# control_board.net
KiCad netlist of a schematic drawn in EAGLE
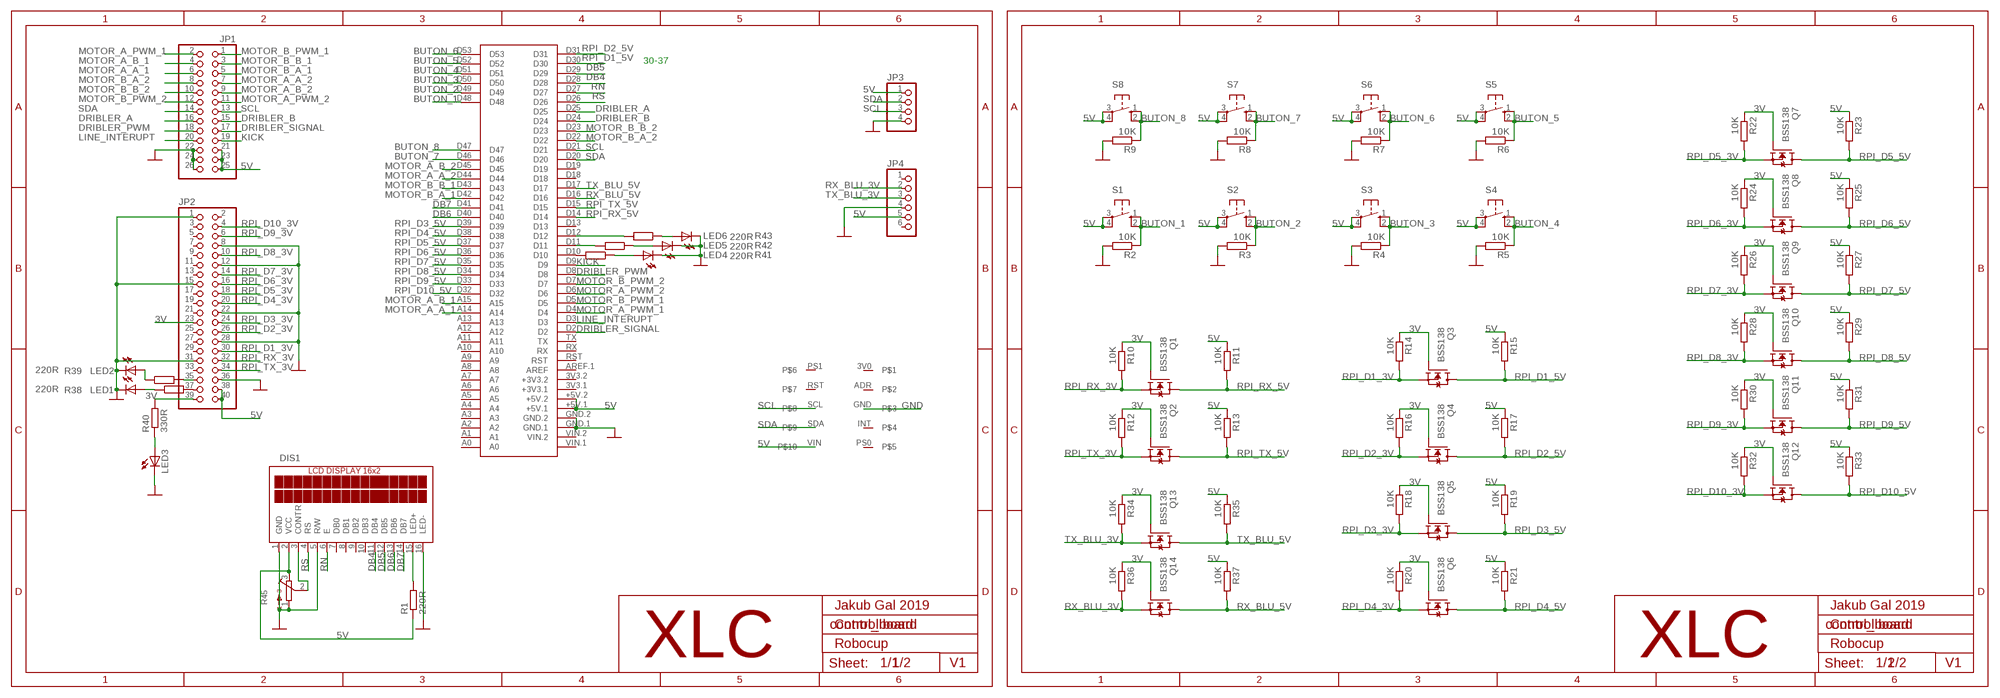
[diagram p0: schematic, sheet 1]

(export (version "E")
  (design (tool "Eeschema 10.0.6"))
  (components
    (comp (ref "DIS1")
      (value "LCD_DISPLEJ_16X2Z")
      (footprint "eagle-import:LCD_DISPLEJ_16X2")
      (libsource (lib "eagle-import") (part "LCD_DISPLEJ_16X2Z"))
    )
    (comp (ref "JP1")
      (value "PINHD-2X13_2.54")
      (footprint "eagle-import:2X13")
      (libsource (lib "eagle-import") (part "PINHD-2X13_2.54"))
    )
    (comp (ref "JP2")
      (value "PINHD-2X20_2.54")
      (footprint "eagle-import:2X20")
      (libsource (lib "eagle-import") (part "PINHD-2X20_2.54"))
    )
    (comp (ref "JP3")
      (value "PINHD-1X4_2.54")
      (footprint "eagle-import:1X04")
      (libsource (lib "eagle-import") (part "PINHD-1X4_2.54"))
    )
    (comp (ref "JP4")
      (value "PINHD-1X6_2.54")
      (footprint "eagle-import:1X06")
      (libsource (lib "eagle-import") (part "PINHD-1X6_2.54"))
    )
    (comp (ref "LED1")
      (value "LEDCHIPLED_0603")
      (footprint "eagle-import:CHIPLED_0603")
      (libsource (lib "eagle-import") (part "LEDCHIPLED_0603"))
    )
    (comp (ref "LED2")
      (value "LEDCHIPLED_0603")
      (footprint "eagle-import:CHIPLED_0603")
      (libsource (lib "eagle-import") (part "LEDCHIPLED_0603"))
    )
    (comp (ref "LED3")
      (value "LEDCHIPLED_0603")
      (footprint "eagle-import:CHIPLED_0603")
      (libsource (lib "eagle-import") (part "LEDCHIPLED_0603"))
    )
    (comp (ref "LED4")
      (value "LEDCHIPLED_0603")
      (footprint "eagle-import:CHIPLED_0603")
      (libsource (lib "eagle-import") (part "LEDCHIPLED_0603"))
    )
    (comp (ref "LED5")
      (value "LEDCHIPLED_0603")
      (footprint "eagle-import:CHIPLED_0603")
      (libsource (lib "eagle-import") (part "LEDCHIPLED_0603"))
    )
    (comp (ref "LED6")
      (value "LEDCHIPLED_0603")
      (footprint "eagle-import:CHIPLED_0603")
      (libsource (lib "eagle-import") (part "LEDCHIPLED_0603"))
    )
    (comp (ref "Q1")
      (value "BSS138")
      (footprint "eagle-import:SOT23")
      (fields (field (name "MF") "Fairchild"))
      (libsource (lib "eagle-import") (part "BSS138"))
    )
    (comp (ref "Q2")
      (value "BSS138")
      (footprint "eagle-import:SOT23")
      (fields (field (name "MF") "Fairchild"))
      (libsource (lib "eagle-import") (part "BSS138"))
    )
    (comp (ref "Q3")
      (value "BSS138")
      (footprint "eagle-import:SOT23")
      (fields (field (name "MF") "Fairchild"))
      (libsource (lib "eagle-import") (part "BSS138"))
    )
    (comp (ref "Q4")
      (value "BSS138")
      (footprint "eagle-import:SOT23")
      (fields (field (name "MF") "Fairchild"))
      (libsource (lib "eagle-import") (part "BSS138"))
    )
    (comp (ref "Q5")
      (value "BSS138")
      (footprint "eagle-import:SOT23")
      (fields (field (name "MF") "Fairchild"))
      (libsource (lib "eagle-import") (part "BSS138"))
    )
    (comp (ref "Q6")
      (value "BSS138")
      (footprint "eagle-import:SOT23")
      (fields (field (name "MF") "Fairchild"))
      (libsource (lib "eagle-import") (part "BSS138"))
    )
    (comp (ref "Q7")
      (value "BSS138")
      (footprint "eagle-import:SOT23")
      (fields (field (name "MF") "Fairchild"))
      (libsource (lib "eagle-import") (part "BSS138"))
    )
    (comp (ref "Q8")
      (value "BSS138")
      (footprint "eagle-import:SOT23")
      (fields (field (name "MF") "Fairchild"))
      (libsource (lib "eagle-import") (part "BSS138"))
    )
    (comp (ref "Q9")
      (value "BSS138")
      (footprint "eagle-import:SOT23")
      (fields (field (name "MF") "Fairchild"))
      (libsource (lib "eagle-import") (part "BSS138"))
    )
    (comp (ref "Q10")
      (value "BSS138")
      (footprint "eagle-import:SOT23")
      (fields (field (name "MF") "Fairchild"))
      (libsource (lib "eagle-import") (part "BSS138"))
    )
    (comp (ref "Q11")
      (value "BSS138")
      (footprint "eagle-import:SOT23")
      (fields (field (name "MF") "Fairchild"))
      (libsource (lib "eagle-import") (part "BSS138"))
    )
    (comp (ref "Q12")
      (value "BSS138")
      (footprint "eagle-import:SOT23")
      (fields (field (name "MF") "Fairchild"))
      (libsource (lib "eagle-import") (part "BSS138"))
    )
    (comp (ref "Q13")
      (value "BSS138")
      (footprint "eagle-import:SOT23")
      (fields (field (name "MF") "Fairchild"))
      (libsource (lib "eagle-import") (part "BSS138"))
    )
    (comp (ref "Q14")
      (value "BSS138")
      (footprint "eagle-import:SOT23")
      (fields (field (name "MF") "Fairchild"))
      (libsource (lib "eagle-import") (part "BSS138"))
    )
    (comp (ref "R1")
      (value "220R")
      (footprint "eagle-import:R0603")
      (libsource (lib "eagle-import") (part "R-EU_R0603"))
    )
    (comp (ref "R2")
      (value "10K")
      (footprint "eagle-import:R0603")
      (libsource (lib "eagle-import") (part "R-EU_R0603"))
    )
    (comp (ref "R3")
      (value "10K")
      (footprint "eagle-import:R0603")
      (libsource (lib "eagle-import") (part "R-EU_R0603"))
    )
    (comp (ref "R4")
      (value "10K")
      (footprint "eagle-import:R0603")
      (libsource (lib "eagle-import") (part "R-EU_R0603"))
    )
    (comp (ref "R5")
      (value "10K")
      (footprint "eagle-import:R0603")
      (libsource (lib "eagle-import") (part "R-EU_R0603"))
    )
    (comp (ref "R6")
      (value "10K")
      (footprint "eagle-import:R0603")
      (libsource (lib "eagle-import") (part "R-EU_R0603"))
    )
    (comp (ref "R7")
      (value "10K")
      (footprint "eagle-import:R0603")
      (libsource (lib "eagle-import") (part "R-EU_R0603"))
    )
    (comp (ref "R8")
      (value "10K")
      (footprint "eagle-import:R0603")
      (libsource (lib "eagle-import") (part "R-EU_R0603"))
    )
    (comp (ref "R9")
      (value "10K")
      (footprint "eagle-import:R0603")
      (libsource (lib "eagle-import") (part "R-EU_R0603"))
    )
    (comp (ref "R10")
      (value "10K")
      (footprint "eagle-import:R0603")
      (libsource (lib "eagle-import") (part "R-EU_R0603"))
    )
    (comp (ref "R11")
      (value "10K")
      (footprint "eagle-import:R0603")
      (libsource (lib "eagle-import") (part "R-EU_R0603"))
    )
    (comp (ref "R12")
      (value "10K")
      (footprint "eagle-import:R0603")
      (libsource (lib "eagle-import") (part "R-EU_R0603"))
    )
    (comp (ref "R13")
      (value "10K")
      (footprint "eagle-import:R0603")
      (libsource (lib "eagle-import") (part "R-EU_R0603"))
    )
    (comp (ref "R14")
      (value "10K")
      (footprint "eagle-import:R0603")
      (libsource (lib "eagle-import") (part "R-EU_R0603"))
    )
    (comp (ref "R15")
      (value "10K")
      (footprint "eagle-import:R0603")
      (libsource (lib "eagle-import") (part "R-EU_R0603"))
    )
    (comp (ref "R16")
      (value "10K")
      (footprint "eagle-import:R0603")
      (libsource (lib "eagle-import") (part "R-EU_R0603"))
    )
    (comp (ref "R17")
      (value "10K")
      (footprint "eagle-import:R0603")
      (libsource (lib "eagle-import") (part "R-EU_R0603"))
    )
    (comp (ref "R18")
      (value "10K")
      (footprint "eagle-import:R0603")
      (libsource (lib "eagle-import") (part "R-EU_R0603"))
    )
    (comp (ref "R19")
      (value "10K")
      (footprint "eagle-import:R0603")
      (libsource (lib "eagle-import") (part "R-EU_R0603"))
    )
    (comp (ref "R20")
      (value "10K")
      (footprint "eagle-import:R0603")
      (libsource (lib "eagle-import") (part "R-EU_R0603"))
    )
    (comp (ref "R21")
      (value "10K")
      (footprint "eagle-import:R0603")
      (libsource (lib "eagle-import") (part "R-EU_R0603"))
    )
    (comp (ref "R22")
      (value "10K")
      (footprint "eagle-import:R0603")
      (libsource (lib "eagle-import") (part "R-EU_R0603"))
    )
    (comp (ref "R23")
      (value "10K")
      (footprint "eagle-import:R0603")
      (libsource (lib "eagle-import") (part "R-EU_R0603"))
    )
    (comp (ref "R24")
      (value "10K")
      (footprint "eagle-import:R0603")
      (libsource (lib "eagle-import") (part "R-EU_R0603"))
    )
    (comp (ref "R25")
      (value "10K")
      (footprint "eagle-import:R0603")
      (libsource (lib "eagle-import") (part "R-EU_R0603"))
    )
    (comp (ref "R26")
      (value "10K")
      (footprint "eagle-import:R0603")
      (libsource (lib "eagle-import") (part "R-EU_R0603"))
    )
    (comp (ref "R27")
      (value "10K")
      (footprint "eagle-import:R0603")
      (libsource (lib "eagle-import") (part "R-EU_R0603"))
    )
    (comp (ref "R28")
      (value "10K")
      (footprint "eagle-import:R0603")
      (libsource (lib "eagle-import") (part "R-EU_R0603"))
    )
    (comp (ref "R29")
      (value "10K")
      (footprint "eagle-import:R0603")
      (libsource (lib "eagle-import") (part "R-EU_R0603"))
    )
    (comp (ref "R30")
      (value "10K")
      (footprint "eagle-import:R0603")
      (libsource (lib "eagle-import") (part "R-EU_R0603"))
    )
    (comp (ref "R31")
      (value "10K")
      (footprint "eagle-import:R0603")
      (libsource (lib "eagle-import") (part "R-EU_R0603"))
    )
    (comp (ref "R32")
      (value "10K")
      (footprint "eagle-import:R0603")
      (libsource (lib "eagle-import") (part "R-EU_R0603"))
    )
    (comp (ref "R33")
      (value "10K")
      (footprint "eagle-import:R0603")
      (libsource (lib "eagle-import") (part "R-EU_R0603"))
    )
    (comp (ref "R34")
      (value "10K")
      (footprint "eagle-import:R0603")
      (libsource (lib "eagle-import") (part "R-EU_R0603"))
    )
    (comp (ref "R35")
      (value "10K")
      (footprint "eagle-import:R0603")
      (libsource (lib "eagle-import") (part "R-EU_R0603"))
    )
    (comp (ref "R36")
      (value "10K")
      (footprint "eagle-import:R0603")
      (libsource (lib "eagle-import") (part "R-EU_R0603"))
    )
    (comp (ref "R37")
      (value "10K")
      (footprint "eagle-import:R0603")
      (libsource (lib "eagle-import") (part "R-EU_R0603"))
    )
    (comp (ref "R38")
      (value "220R")
      (footprint "eagle-import:R0603")
      (libsource (lib "eagle-import") (part "R-EU_R0603"))
    )
    (comp (ref "R39")
      (value "220R")
      (footprint "eagle-import:R0603")
      (libsource (lib "eagle-import") (part "R-EU_R0603"))
    )
    (comp (ref "R40")
      (value "330R")
      (footprint "eagle-import:R0603")
      (libsource (lib "eagle-import") (part "R-EU_R0603"))
    )
    (comp (ref "R41")
      (value "220R")
      (footprint "eagle-import:R0603")
      (libsource (lib "eagle-import") (part "R-EU_R0603"))
    )
    (comp (ref "R42")
      (value "220R")
      (footprint "eagle-import:R0603")
      (libsource (lib "eagle-import") (part "R-EU_R0603"))
    )
    (comp (ref "R43")
      (value "220R")
      (footprint "eagle-import:R0603")
      (libsource (lib "eagle-import") (part "R-EU_R0603"))
    )
    (comp (ref "R45")
      (value "3362P")
      (footprint "eagle-import:3362P")
      (libsource (lib "eagle-import") (part "3362P"))
    )
    (comp (ref "S1")
      (value "10-XX")
      (footprint "eagle-import:B3F-10XX")
      (fields (field (name "MPN") "B3F-1000"))
      (libsource (lib "eagle-import") (part "10-XX"))
    )
    (comp (ref "S2")
      (value "10-XX")
      (footprint "eagle-import:B3F-10XX")
      (fields (field (name "MPN") "B3F-1000"))
      (libsource (lib "eagle-import") (part "10-XX"))
    )
    (comp (ref "S3")
      (value "10-XX")
      (footprint "eagle-import:B3F-10XX")
      (fields (field (name "MPN") "B3F-1000"))
      (libsource (lib "eagle-import") (part "10-XX"))
    )
    (comp (ref "S4")
      (value "10-XX")
      (footprint "eagle-import:B3F-10XX")
      (fields (field (name "MPN") "B3F-1000"))
      (libsource (lib "eagle-import") (part "10-XX"))
    )
    (comp (ref "S5")
      (value "10-XX")
      (footprint "eagle-import:B3F-10XX")
      (fields (field (name "MPN") "B3F-1000"))
      (libsource (lib "eagle-import") (part "10-XX"))
    )
    (comp (ref "S6")
      (value "10-XX")
      (footprint "eagle-import:B3F-10XX")
      (fields (field (name "MPN") "B3F-1000"))
      (libsource (lib "eagle-import") (part "10-XX"))
    )
    (comp (ref "S7")
      (value "10-XX")
      (footprint "eagle-import:B3F-10XX")
      (fields (field (name "MPN") "B3F-1000"))
      (libsource (lib "eagle-import") (part "10-XX"))
    )
    (comp (ref "S8")
      (value "10-XX")
      (footprint "eagle-import:B3F-10XX")
      (fields (field (name "MPN") "B3F-1000"))
      (libsource (lib "eagle-import") (part "10-XX"))
    )
    (comp (ref "U$1")
      (value "MEGA2560_MIKRO")
      (footprint "eagle-import:MEGA2560_MIKRO")
      (libsource (lib "eagle-import") (part "MEGA2560_MIKRO"))
    )
    (comp (ref "U$2")
      (value "BNO055")
      (footprint "eagle-import:BNO005")
      (libsource (lib "eagle-import") (part "BNO055"))
    )
  )
  (nets
    (net (code "1") (name "/3V") (class "Default")
      (node (ref "JP2") (pin "23") (pinfunction "23_23") (pintype "passive"))
      (node (ref "JP2") (pin "39") (pinfunction "39_39") (pintype "passive"))
      (node (ref "Q1") (pin "1") (pinfunction "G_1") (pintype "passive"))
      (node (ref "Q10") (pin "1") (pinfunction "G_1") (pintype "passive"))
      (node (ref "Q11") (pin "1") (pinfunction "G_1") (pintype "passive"))
      (node (ref "Q12") (pin "1") (pinfunction "G_1") (pintype "passive"))
      (node (ref "Q13") (pin "1") (pinfunction "G_1") (pintype "passive"))
      (node (ref "Q14") (pin "1") (pinfunction "G_1") (pintype "passive"))
      (node (ref "Q2") (pin "1") (pinfunction "G_1") (pintype "passive"))
      (node (ref "Q3") (pin "1") (pinfunction "G_1") (pintype "passive"))
      (node (ref "Q4") (pin "1") (pinfunction "G_1") (pintype "passive"))
      (node (ref "Q5") (pin "1") (pinfunction "G_1") (pintype "passive"))
      (node (ref "Q6") (pin "1") (pinfunction "G_1") (pintype "passive"))
      (node (ref "Q7") (pin "1") (pinfunction "G_1") (pintype "passive"))
      (node (ref "Q8") (pin "1") (pinfunction "G_1") (pintype "passive"))
      (node (ref "Q9") (pin "1") (pinfunction "G_1") (pintype "passive"))
      (node (ref "R10") (pin "1") (pinfunction "1_1") (pintype "passive"))
      (node (ref "R12") (pin "1") (pinfunction "1_1") (pintype "passive"))
      (node (ref "R14") (pin "1") (pinfunction "1_1") (pintype "passive"))
      (node (ref "R16") (pin "1") (pinfunction "1_1") (pintype "passive"))
      (node (ref "R18") (pin "1") (pinfunction "1_1") (pintype "passive"))
      (node (ref "R20") (pin "1") (pinfunction "1_1") (pintype "passive"))
      (node (ref "R22") (pin "1") (pinfunction "1_1") (pintype "passive"))
      (node (ref "R24") (pin "1") (pinfunction "1_1") (pintype "passive"))
      (node (ref "R26") (pin "1") (pinfunction "1_1") (pintype "passive"))
      (node (ref "R28") (pin "1") (pinfunction "1_1") (pintype "passive"))
      (node (ref "R30") (pin "1") (pinfunction "1_1") (pintype "passive"))
      (node (ref "R32") (pin "1") (pinfunction "1_1") (pintype "passive"))
      (node (ref "R34") (pin "1") (pinfunction "1_1") (pintype "passive"))
      (node (ref "R36") (pin "1") (pinfunction "1_1") (pintype "passive"))
      (node (ref "R40") (pin "2") (pinfunction "2_2") (pintype "passive"))
    )
    (net (code "2") (name "/5V") (class "Default")
      (node (ref "DIS1") (pin "2") (pinfunction "VCC_2") (pintype "power_in"))
      (node (ref "JP1") (pin "21") (pinfunction "21_21") (pintype "passive"))
      (node (ref "JP1") (pin "23") (pinfunction "23_23") (pintype "passive"))
      (node (ref "JP1") (pin "25") (pinfunction "25_25") (pintype "passive"))
      (node (ref "JP2") (pin "38") (pinfunction "38_38") (pintype "passive"))
      (node (ref "JP2") (pin "40") (pinfunction "40_40") (pintype "passive"))
      (node (ref "JP3") (pin "1") (pinfunction "1_1") (pintype "passive"))
      (node (ref "JP4") (pin "5") (pinfunction "5_5") (pintype "passive"))
      (node (ref "R1") (pin "1") (pinfunction "1_1") (pintype "passive"))
      (node (ref "R11") (pin "1") (pinfunction "1_1") (pintype "passive"))
      (node (ref "R13") (pin "1") (pinfunction "1_1") (pintype "passive"))
      (node (ref "R15") (pin "1") (pinfunction "1_1") (pintype "passive"))
      (node (ref "R17") (pin "1") (pinfunction "1_1") (pintype "passive"))
      (node (ref "R19") (pin "1") (pinfunction "1_1") (pintype "passive"))
      (node (ref "R21") (pin "1") (pinfunction "1_1") (pintype "passive"))
      (node (ref "R23") (pin "1") (pinfunction "1_1") (pintype "passive"))
      (node (ref "R25") (pin "1") (pinfunction "1_1") (pintype "passive"))
      (node (ref "R27") (pin "1") (pinfunction "1_1") (pintype "passive"))
      (node (ref "R29") (pin "1") (pinfunction "1_1") (pintype "passive"))
      (node (ref "R31") (pin "1") (pinfunction "1_1") (pintype "passive"))
      (node (ref "R33") (pin "1") (pinfunction "1_1") (pintype "passive"))
      (node (ref "R35") (pin "1") (pinfunction "1_1") (pintype "passive"))
      (node (ref "R37") (pin "1") (pinfunction "1_1") (pintype "passive"))
      (node (ref "R45") (pin "3") (pinfunction "3_3") (pintype "passive"))
      (node (ref "S1") (pin "3") (pinfunction "P_3") (pintype "passive"))
      (node (ref "S1") (pin "4") (pinfunction "P1_4") (pintype "passive"))
      (node (ref "S2") (pin "3") (pinfunction "P_3") (pintype "passive"))
      (node (ref "S2") (pin "4") (pinfunction "P1_4") (pintype "passive"))
      (node (ref "S3") (pin "3") (pinfunction "P_3") (pintype "passive"))
      (node (ref "S3") (pin "4") (pinfunction "P1_4") (pintype "passive"))
      (node (ref "S4") (pin "3") (pinfunction "P_3") (pintype "passive"))
      (node (ref "S4") (pin "4") (pinfunction "P1_4") (pintype "passive"))
      (node (ref "S5") (pin "3") (pinfunction "P_3") (pintype "passive"))
      (node (ref "S5") (pin "4") (pinfunction "P1_4") (pintype "passive"))
      (node (ref "S6") (pin "3") (pinfunction "P_3") (pintype "passive"))
      (node (ref "S6") (pin "4") (pinfunction "P1_4") (pintype "passive"))
      (node (ref "S7") (pin "3") (pinfunction "P_3") (pintype "passive"))
      (node (ref "S7") (pin "4") (pinfunction "P1_4") (pintype "passive"))
      (node (ref "S8") (pin "3") (pinfunction "P_3") (pintype "passive"))
      (node (ref "S8") (pin "4") (pinfunction "P1_4") (pintype "passive"))
      (node (ref "U$1") (pin "+5V.1") (pinfunction "+5V.1_+5V.1") (pintype "bidirectional"))
      (node (ref "U$1") (pin "+5V.2") (pinfunction "+5V.2_+5V.2") (pintype "bidirectional"))
      (node (ref "U$2") (pin "VIN") (pinfunction "P$10_VIN") (pintype "bidirectional"))
    )
    (net (code "3") (name "/BUTON_1") (class "Default")
      (node (ref "R2") (pin "1") (pinfunction "1_1") (pintype "passive"))
      (node (ref "S1") (pin "1") (pinfunction "S_1") (pintype "passive"))
      (node (ref "S1") (pin "2") (pinfunction "S1_2") (pintype "passive"))
      (node (ref "U$1") (pin "D48") (pinfunction "D48_D48") (pintype "bidirectional"))
    )
    (net (code "4") (name "/BUTON_2") (class "Default")
      (node (ref "R3") (pin "1") (pinfunction "1_1") (pintype "passive"))
      (node (ref "S2") (pin "1") (pinfunction "S_1") (pintype "passive"))
      (node (ref "S2") (pin "2") (pinfunction "S1_2") (pintype "passive"))
      (node (ref "U$1") (pin "D49") (pinfunction "D49_D49") (pintype "bidirectional"))
    )
    (net (code "5") (name "/BUTON_3") (class "Default")
      (node (ref "R4") (pin "1") (pinfunction "1_1") (pintype "passive"))
      (node (ref "S3") (pin "1") (pinfunction "S_1") (pintype "passive"))
      (node (ref "S3") (pin "2") (pinfunction "S1_2") (pintype "passive"))
      (node (ref "U$1") (pin "D50") (pinfunction "D50_D50") (pintype "bidirectional"))
    )
    (net (code "6") (name "/BUTON_4") (class "Default")
      (node (ref "R5") (pin "1") (pinfunction "1_1") (pintype "passive"))
      (node (ref "S4") (pin "1") (pinfunction "S_1") (pintype "passive"))
      (node (ref "S4") (pin "2") (pinfunction "S1_2") (pintype "passive"))
      (node (ref "U$1") (pin "D51") (pinfunction "D51_D51") (pintype "bidirectional"))
    )
    (net (code "7") (name "/BUTON_5") (class "Default")
      (node (ref "R6") (pin "1") (pinfunction "1_1") (pintype "passive"))
      (node (ref "S5") (pin "1") (pinfunction "S_1") (pintype "passive"))
      (node (ref "S5") (pin "2") (pinfunction "S1_2") (pintype "passive"))
      (node (ref "U$1") (pin "D52") (pinfunction "D52_D52") (pintype "bidirectional"))
    )
    (net (code "8") (name "/BUTON_6") (class "Default")
      (node (ref "R7") (pin "1") (pinfunction "1_1") (pintype "passive"))
      (node (ref "S6") (pin "1") (pinfunction "S_1") (pintype "passive"))
      (node (ref "S6") (pin "2") (pinfunction "S1_2") (pintype "passive"))
      (node (ref "U$1") (pin "D53") (pinfunction "D53_D53") (pintype "bidirectional"))
    )
    (net (code "9") (name "/BUTON_7") (class "Default")
      (node (ref "R8") (pin "1") (pinfunction "1_1") (pintype "passive"))
      (node (ref "S7") (pin "1") (pinfunction "S_1") (pintype "passive"))
      (node (ref "S7") (pin "2") (pinfunction "S1_2") (pintype "passive"))
      (node (ref "U$1") (pin "D46") (pinfunction "D46_D46") (pintype "bidirectional"))
    )
    (net (code "10") (name "/BUTON_8") (class "Default")
      (node (ref "R9") (pin "1") (pinfunction "1_1") (pintype "passive"))
      (node (ref "S8") (pin "1") (pinfunction "S_1") (pintype "passive"))
      (node (ref "S8") (pin "2") (pinfunction "S1_2") (pintype "passive"))
      (node (ref "U$1") (pin "D47") (pinfunction "D47_D47") (pintype "bidirectional"))
    )
    (net (code "11") (name "/DB4") (class "Default")
      (node (ref "DIS1") (pin "11") (pinfunction "DB4_11") (pintype "bidirectional"))
      (node (ref "U$1") (pin "D28") (pinfunction "D28_D28") (pintype "bidirectional"))
    )
    (net (code "12") (name "/DB5") (class "Default")
      (node (ref "DIS1") (pin "12") (pinfunction "DB5_12") (pintype "bidirectional"))
      (node (ref "U$1") (pin "D29") (pinfunction "D29_D29") (pintype "bidirectional"))
    )
    (net (code "13") (name "/DB6") (class "Default")
      (node (ref "DIS1") (pin "13") (pinfunction "DB6_13") (pintype "bidirectional"))
      (node (ref "U$1") (pin "D40") (pinfunction "D40_D40") (pintype "bidirectional"))
    )
    (net (code "14") (name "/DB7") (class "Default")
      (node (ref "DIS1") (pin "14") (pinfunction "DB7_14") (pintype "bidirectional"))
      (node (ref "U$1") (pin "D41") (pinfunction "D41_D41") (pintype "bidirectional"))
    )
    (net (code "15") (name "/DRIBLER_A") (class "Default")
      (node (ref "JP1") (pin "16") (pinfunction "16_16") (pintype "passive"))
      (node (ref "U$1") (pin "D25") (pinfunction "D25_D25") (pintype "bidirectional"))
    )
    (net (code "16") (name "/DRIBLER_B") (class "Default")
      (node (ref "JP1") (pin "15") (pinfunction "15_15") (pintype "passive"))
      (node (ref "U$1") (pin "D24") (pinfunction "D24_D24") (pintype "bidirectional"))
    )
    (net (code "17") (name "/DRIBLER_PWM") (class "Default")
      (node (ref "JP1") (pin "18") (pinfunction "18_18") (pintype "passive"))
      (node (ref "U$1") (pin "D8") (pinfunction "D8_D8") (pintype "bidirectional"))
    )
    (net (code "18") (name "/DRIBLER_SIGNAL") (class "Default")
      (node (ref "JP1") (pin "17") (pinfunction "17_17") (pintype "passive"))
      (node (ref "U$1") (pin "D2") (pinfunction "D2_D2") (pintype "bidirectional"))
    )
    (net (code "19") (name "/KICK") (class "Default")
      (node (ref "JP1") (pin "19") (pinfunction "19_19") (pintype "passive"))
      (node (ref "U$1") (pin "D9") (pinfunction "D9_D9") (pintype "bidirectional"))
    )
    (net (code "20") (name "/LINE_INTERUPT") (class "Default")
      (node (ref "JP1") (pin "20") (pinfunction "20_20") (pintype "passive"))
      (node (ref "U$1") (pin "D3") (pinfunction "D3_D3") (pintype "bidirectional"))
    )
    (net (code "21") (name "/MOTOR_A_A_1") (class "Default")
      (node (ref "JP1") (pin "6") (pinfunction "6_6") (pintype "passive"))
      (node (ref "U$1") (pin "A14") (pinfunction "A14_A14") (pintype "bidirectional"))
    )
    (net (code "22") (name "/MOTOR_A_A_2") (class "Default")
      (node (ref "JP1") (pin "7") (pinfunction "7_7") (pintype "passive"))
      (node (ref "U$1") (pin "D44") (pinfunction "D44_D44") (pintype "bidirectional"))
    )
    (net (code "23") (name "/MOTOR_A_B_1") (class "Default")
      (node (ref "JP1") (pin "4") (pinfunction "4_4") (pintype "passive"))
      (node (ref "U$1") (pin "A15") (pinfunction "A15_A15") (pintype "bidirectional"))
    )
    (net (code "24") (name "/MOTOR_A_B_2") (class "Default")
      (node (ref "JP1") (pin "9") (pinfunction "9_9") (pintype "passive"))
      (node (ref "U$1") (pin "D45") (pinfunction "D45_D45") (pintype "bidirectional"))
    )
    (net (code "25") (name "/MOTOR_A_PWM_1") (class "Default")
      (node (ref "JP1") (pin "2") (pinfunction "2_2") (pintype "passive"))
      (node (ref "U$1") (pin "D4") (pinfunction "D4_D4") (pintype "bidirectional"))
    )
    (net (code "26") (name "/MOTOR_A_PWM_2") (class "Default")
      (node (ref "JP1") (pin "11") (pinfunction "11_11") (pintype "passive"))
      (node (ref "U$1") (pin "D6") (pinfunction "D6_D6") (pintype "bidirectional"))
    )
    (net (code "27") (name "/MOTOR_B_A_1") (class "Default")
      (node (ref "JP1") (pin "5") (pinfunction "5_5") (pintype "passive"))
      (node (ref "U$1") (pin "D42") (pinfunction "D42_D42") (pintype "bidirectional"))
    )
    (net (code "28") (name "/MOTOR_B_A_2") (class "Default")
      (node (ref "JP1") (pin "8") (pinfunction "8_8") (pintype "passive"))
      (node (ref "U$1") (pin "D22") (pinfunction "D22_D22") (pintype "bidirectional"))
    )
    (net (code "29") (name "/MOTOR_B_B_1") (class "Default")
      (node (ref "JP1") (pin "3") (pinfunction "3_3") (pintype "passive"))
      (node (ref "U$1") (pin "D43") (pinfunction "D43_D43") (pintype "bidirectional"))
    )
    (net (code "30") (name "/MOTOR_B_B_2") (class "Default")
      (node (ref "JP1") (pin "10") (pinfunction "10_10") (pintype "passive"))
      (node (ref "U$1") (pin "D23") (pinfunction "D23_D23") (pintype "bidirectional"))
    )
    (net (code "31") (name "/MOTOR_B_PWM_1") (class "Default")
      (node (ref "JP1") (pin "1") (pinfunction "1_1") (pintype "passive"))
      (node (ref "U$1") (pin "D5") (pinfunction "D5_D5") (pintype "bidirectional"))
    )
    (net (code "32") (name "/MOTOR_B_PWM_2") (class "Default")
      (node (ref "JP1") (pin "12") (pinfunction "12_12") (pintype "passive"))
      (node (ref "U$1") (pin "D7") (pinfunction "D7_D7") (pintype "bidirectional"))
    )
    (net (code "33") (name "/RN") (class "Default")
      (node (ref "DIS1") (pin "6") (pinfunction "E_6") (pintype "input"))
      (node (ref "U$1") (pin "D27") (pinfunction "D27_D27") (pintype "bidirectional"))
    )
    (net (code "34") (name "/RPI_D1_3V") (class "Default")
      (node (ref "JP2") (pin "30") (pinfunction "30_30") (pintype "passive"))
      (node (ref "Q3") (pin "2") (pinfunction "S_2") (pintype "passive"))
      (node (ref "R14") (pin "2") (pinfunction "2_2") (pintype "passive"))
    )
    (net (code "35") (name "/RPI_D1_5V") (class "Default")
      (node (ref "Q3") (pin "3") (pinfunction "D_3") (pintype "passive"))
      (node (ref "R15") (pin "2") (pinfunction "2_2") (pintype "passive"))
      (node (ref "U$1") (pin "D30") (pinfunction "D30_D30") (pintype "bidirectional"))
    )
    (net (code "36") (name "/RPI_D2_3V") (class "Default")
      (node (ref "JP2") (pin "26") (pinfunction "26_26") (pintype "passive"))
      (node (ref "Q4") (pin "2") (pinfunction "S_2") (pintype "passive"))
      (node (ref "R16") (pin "2") (pinfunction "2_2") (pintype "passive"))
    )
    (net (code "37") (name "/RPI_D2_5V") (class "Default")
      (node (ref "Q4") (pin "3") (pinfunction "D_3") (pintype "passive"))
      (node (ref "R17") (pin "2") (pinfunction "2_2") (pintype "passive"))
      (node (ref "U$1") (pin "D31") (pinfunction "D31_D31") (pintype "bidirectional"))
    )
    (net (code "38") (name "/RPI_D3_3V") (class "Default")
      (node (ref "JP2") (pin "24") (pinfunction "24_24") (pintype "passive"))
      (node (ref "Q5") (pin "2") (pinfunction "S_2") (pintype "passive"))
      (node (ref "R18") (pin "2") (pinfunction "2_2") (pintype "passive"))
    )
    (net (code "39") (name "/RPI_D3_5V") (class "Default")
      (node (ref "Q5") (pin "3") (pinfunction "D_3") (pintype "passive"))
      (node (ref "R19") (pin "2") (pinfunction "2_2") (pintype "passive"))
      (node (ref "U$1") (pin "D39") (pinfunction "D39_D39") (pintype "bidirectional"))
    )
    (net (code "40") (name "/RPI_D4_3V") (class "Default")
      (node (ref "JP2") (pin "20") (pinfunction "20_20") (pintype "passive"))
      (node (ref "Q6") (pin "2") (pinfunction "S_2") (pintype "passive"))
      (node (ref "R20") (pin "2") (pinfunction "2_2") (pintype "passive"))
    )
    (net (code "41") (name "/RPI_D4_5V") (class "Default")
      (node (ref "Q6") (pin "3") (pinfunction "D_3") (pintype "passive"))
      (node (ref "R21") (pin "2") (pinfunction "2_2") (pintype "passive"))
      (node (ref "U$1") (pin "D38") (pinfunction "D38_D38") (pintype "bidirectional"))
    )
    (net (code "42") (name "/RPI_D5_3V") (class "Default")
      (node (ref "JP2") (pin "18") (pinfunction "18_18") (pintype "passive"))
      (node (ref "Q7") (pin "2") (pinfunction "S_2") (pintype "passive"))
      (node (ref "R22") (pin "2") (pinfunction "2_2") (pintype "passive"))
    )
    (net (code "43") (name "/RPI_D5_5V") (class "Default")
      (node (ref "Q7") (pin "3") (pinfunction "D_3") (pintype "passive"))
      (node (ref "R23") (pin "2") (pinfunction "2_2") (pintype "passive"))
      (node (ref "U$1") (pin "D37") (pinfunction "D37_D37") (pintype "bidirectional"))
    )
    (net (code "44") (name "/RPI_D6_3V") (class "Default")
      (node (ref "JP2") (pin "16") (pinfunction "16_16") (pintype "passive"))
      (node (ref "Q8") (pin "2") (pinfunction "S_2") (pintype "passive"))
      (node (ref "R24") (pin "2") (pinfunction "2_2") (pintype "passive"))
    )
    (net (code "45") (name "/RPI_D6_5V") (class "Default")
      (node (ref "Q8") (pin "3") (pinfunction "D_3") (pintype "passive"))
      (node (ref "R25") (pin "2") (pinfunction "2_2") (pintype "passive"))
      (node (ref "U$1") (pin "D36") (pinfunction "D36_D36") (pintype "bidirectional"))
    )
    (net (code "46") (name "/RPI_D7_3V") (class "Default")
      (node (ref "JP2") (pin "14") (pinfunction "14_14") (pintype "passive"))
      (node (ref "Q9") (pin "2") (pinfunction "S_2") (pintype "passive"))
      (node (ref "R26") (pin "2") (pinfunction "2_2") (pintype "passive"))
    )
    (net (code "47") (name "/RPI_D7_5V") (class "Default")
      (node (ref "Q9") (pin "3") (pinfunction "D_3") (pintype "passive"))
      (node (ref "R27") (pin "2") (pinfunction "2_2") (pintype "passive"))
      (node (ref "U$1") (pin "D35") (pinfunction "D35_D35") (pintype "bidirectional"))
    )
    (net (code "48") (name "/RPI_D8_3V") (class "Default")
      (node (ref "JP2") (pin "10") (pinfunction "10_10") (pintype "passive"))
      (node (ref "Q10") (pin "2") (pinfunction "S_2") (pintype "passive"))
      (node (ref "R28") (pin "2") (pinfunction "2_2") (pintype "passive"))
    )
    (net (code "49") (name "/RPI_D8_5V") (class "Default")
      (node (ref "Q10") (pin "3") (pinfunction "D_3") (pintype "passive"))
      (node (ref "R29") (pin "2") (pinfunction "2_2") (pintype "passive"))
      (node (ref "U$1") (pin "D34") (pinfunction "D34_D34") (pintype "bidirectional"))
    )
    (net (code "50") (name "/RPI_D9_3V") (class "Default")
      (node (ref "JP2") (pin "6") (pinfunction "6_6") (pintype "passive"))
      (node (ref "Q11") (pin "2") (pinfunction "S_2") (pintype "passive"))
      (node (ref "R30") (pin "2") (pinfunction "2_2") (pintype "passive"))
    )
    (net (code "51") (name "/RPI_D9_5V") (class "Default")
      (node (ref "Q11") (pin "3") (pinfunction "D_3") (pintype "passive"))
      (node (ref "R31") (pin "2") (pinfunction "2_2") (pintype "passive"))
      (node (ref "U$1") (pin "D33") (pinfunction "D33_D33") (pintype "bidirectional"))
    )
    (net (code "52") (name "/RPI_D10_3V") (class "Default")
      (node (ref "JP2") (pin "4") (pinfunction "4_4") (pintype "passive"))
      (node (ref "Q12") (pin "2") (pinfunction "S_2") (pintype "passive"))
      (node (ref "R32") (pin "2") (pinfunction "2_2") (pintype "passive"))
    )
    (net (code "53") (name "/RPI_D10_5V") (class "Default")
      (node (ref "Q12") (pin "3") (pinfunction "D_3") (pintype "passive"))
      (node (ref "R33") (pin "2") (pinfunction "2_2") (pintype "passive"))
      (node (ref "U$1") (pin "D32") (pinfunction "D32_D32") (pintype "bidirectional"))
    )
    (net (code "54") (name "/RPI_RX_3V") (class "Default")
      (node (ref "JP2") (pin "32") (pinfunction "32_32") (pintype "passive"))
      (node (ref "Q1") (pin "2") (pinfunction "S_2") (pintype "passive"))
      (node (ref "R10") (pin "2") (pinfunction "2_2") (pintype "passive"))
    )
    (net (code "55") (name "/RPI_RX_5V") (class "Default")
      (node (ref "Q1") (pin "3") (pinfunction "D_3") (pintype "passive"))
      (node (ref "R11") (pin "2") (pinfunction "2_2") (pintype "passive"))
      (node (ref "U$1") (pin "D14") (pinfunction "D14_D14") (pintype "bidirectional"))
    )
    (net (code "56") (name "/RPI_TX_3V") (class "Default")
      (node (ref "JP2") (pin "34") (pinfunction "34_34") (pintype "passive"))
      (node (ref "Q2") (pin "2") (pinfunction "S_2") (pintype "passive"))
      (node (ref "R12") (pin "2") (pinfunction "2_2") (pintype "passive"))
    )
    (net (code "57") (name "/RPI_TX_5V") (class "Default")
      (node (ref "Q2") (pin "3") (pinfunction "D_3") (pintype "passive"))
      (node (ref "R13") (pin "2") (pinfunction "2_2") (pintype "passive"))
      (node (ref "U$1") (pin "D15") (pinfunction "D15_D15") (pintype "bidirectional"))
    )
    (net (code "58") (name "/RS") (class "Default")
      (node (ref "DIS1") (pin "4") (pinfunction "RS_4") (pintype "input"))
      (node (ref "U$1") (pin "D26") (pinfunction "D26_D26") (pintype "bidirectional"))
    )
    (net (code "59") (name "/RX_BLU_3V") (class "Default")
      (node (ref "JP4") (pin "2") (pinfunction "2_2") (pintype "passive"))
      (node (ref "Q14") (pin "2") (pinfunction "S_2") (pintype "passive"))
      (node (ref "R36") (pin "2") (pinfunction "2_2") (pintype "passive"))
    )
    (net (code "60") (name "/RX_BLU_5V") (class "Default")
      (node (ref "Q14") (pin "3") (pinfunction "D_3") (pintype "passive"))
      (node (ref "R37") (pin "2") (pinfunction "2_2") (pintype "passive"))
      (node (ref "U$1") (pin "D16") (pinfunction "D16_D16") (pintype "bidirectional"))
    )
    (net (code "61") (name "/SCL") (class "Default")
      (node (ref "JP1") (pin "13") (pinfunction "13_13") (pintype "passive"))
      (node (ref "JP3") (pin "3") (pinfunction "3_3") (pintype "passive"))
      (node (ref "U$1") (pin "D21") (pinfunction "D21_D21") (pintype "bidirectional"))
      (node (ref "U$2") (pin "SCL") (pinfunction "P$8_SCL") (pintype "bidirectional"))
    )
    (net (code "62") (name "/SDA") (class "Default")
      (node (ref "JP1") (pin "14") (pinfunction "14_14") (pintype "passive"))
      (node (ref "JP3") (pin "2") (pinfunction "2_2") (pintype "passive"))
      (node (ref "U$1") (pin "D20") (pinfunction "D20_D20") (pintype "bidirectional"))
      (node (ref "U$2") (pin "SDA") (pinfunction "P$9_SDA") (pintype "bidirectional"))
    )
    (net (code "63") (name "/TX_BLU_3V") (class "Default")
      (node (ref "JP4") (pin "3") (pinfunction "3_3") (pintype "passive"))
      (node (ref "Q13") (pin "2") (pinfunction "S_2") (pintype "passive"))
      (node (ref "R34") (pin "2") (pinfunction "2_2") (pintype "passive"))
    )
    (net (code "64") (name "/TX_BLU_5V") (class "Default")
      (node (ref "Q13") (pin "3") (pinfunction "D_3") (pintype "passive"))
      (node (ref "R35") (pin "2") (pinfunction "2_2") (pintype "passive"))
      (node (ref "U$1") (pin "D17") (pinfunction "D17_D17") (pintype "bidirectional"))
    )
    (net (code "65") (name "GND") (class "Default")
      (node (ref "DIS1") (pin "1") (pinfunction "GND_1") (pintype "power_in"))
      (node (ref "DIS1") (pin "16") (pinfunction "LED-_16") (pintype "passive"))
      (node (ref "DIS1") (pin "5") (pinfunction "R/W_5") (pintype "input"))
      (node (ref "JP1") (pin "22") (pinfunction "22_22") (pintype "passive"))
      (node (ref "JP1") (pin "24") (pinfunction "24_24") (pintype "passive"))
      (node (ref "JP1") (pin "26") (pinfunction "26_26") (pintype "passive"))
      (node (ref "JP2") (pin "1") (pinfunction "1_1") (pintype "passive"))
      (node (ref "JP2") (pin "12") (pinfunction "12_12") (pintype "passive"))
      (node (ref "JP2") (pin "15") (pinfunction "15_15") (pintype "passive"))
      (node (ref "JP2") (pin "22") (pinfunction "22_22") (pintype "passive"))
      (node (ref "JP2") (pin "28") (pinfunction "28_28") (pintype "passive"))
      (node (ref "JP2") (pin "31") (pinfunction "31_31") (pintype "passive"))
      (node (ref "JP2") (pin "36") (pinfunction "36_36") (pintype "passive"))
      (node (ref "JP2") (pin "8") (pinfunction "8_8") (pintype "passive"))
      (node (ref "JP3") (pin "4") (pinfunction "4_4") (pintype "passive"))
      (node (ref "JP4") (pin "4") (pinfunction "4_4") (pintype "passive"))
      (node (ref "LED1") (pin "C") (pinfunction "C_C") (pintype "passive"))
      (node (ref "LED2") (pin "C") (pinfunction "C_C") (pintype "passive"))
      (node (ref "LED3") (pin "C") (pinfunction "C_C") (pintype "passive"))
      (node (ref "LED4") (pin "C") (pinfunction "C_C") (pintype "passive"))
      (node (ref "LED5") (pin "C") (pinfunction "C_C") (pintype "passive"))
      (node (ref "LED6") (pin "C") (pinfunction "C_C") (pintype "passive"))
      (node (ref "R2") (pin "2") (pinfunction "2_2") (pintype "passive"))
      (node (ref "R3") (pin "2") (pinfunction "2_2") (pintype "passive"))
      (node (ref "R4") (pin "2") (pinfunction "2_2") (pintype "passive"))
      (node (ref "R45") (pin "1") (pinfunction "1_1") (pintype "passive"))
      (node (ref "R5") (pin "2") (pinfunction "2_2") (pintype "passive"))
      (node (ref "R6") (pin "2") (pinfunction "2_2") (pintype "passive"))
      (node (ref "R7") (pin "2") (pinfunction "2_2") (pintype "passive"))
      (node (ref "R8") (pin "2") (pinfunction "2_2") (pintype "passive"))
      (node (ref "R9") (pin "2") (pinfunction "2_2") (pintype "passive"))
      (node (ref "U$1") (pin "GND.1") (pinfunction "GND.1_GND.1") (pintype "bidirectional"))
      (node (ref "U$1") (pin "GND.2") (pinfunction "GND.2_GND.2") (pintype "bidirectional"))
      (node (ref "U$2") (pin "GND") (pinfunction "P$3_GND") (pintype "bidirectional"))
    )
    (net (code "66") (name "Net-(DIS1-CONTR)") (class "Default")
      (node (ref "DIS1") (pin "3") (pinfunction "CONTR_3") (pintype "input"))
      (node (ref "R45") (pin "2") (pinfunction "2_2") (pintype "passive"))
    )
    (net (code "67") (name "Net-(DIS1-LED+)") (class "Default")
      (node (ref "DIS1") (pin "15") (pinfunction "LED+_15") (pintype "passive"))
      (node (ref "R1") (pin "2") (pinfunction "2_2") (pintype "passive"))
    )
    (net (code "68") (name "Net-(JP2-Pad35)") (class "Default")
      (node (ref "JP2") (pin "35") (pinfunction "35_35") (pintype "passive"))
      (node (ref "R39") (pin "2") (pinfunction "2_2") (pintype "passive"))
    )
    (net (code "69") (name "Net-(JP2-Pad37)") (class "Default")
      (node (ref "JP2") (pin "37") (pinfunction "37_37") (pintype "passive"))
      (node (ref "R38") (pin "2") (pinfunction "2_2") (pintype "passive"))
    )
    (net (code "70") (name "Net-(LED1-PadA)") (class "Default")
      (node (ref "LED1") (pin "A") (pinfunction "A_A") (pintype "passive"))
      (node (ref "R38") (pin "1") (pinfunction "1_1") (pintype "passive"))
    )
    (net (code "71") (name "Net-(LED2-PadA)") (class "Default")
      (node (ref "LED2") (pin "A") (pinfunction "A_A") (pintype "passive"))
      (node (ref "R39") (pin "1") (pinfunction "1_1") (pintype "passive"))
    )
    (net (code "72") (name "Net-(LED3-PadA)") (class "Default")
      (node (ref "LED3") (pin "A") (pinfunction "A_A") (pintype "passive"))
      (node (ref "R40") (pin "1") (pinfunction "1_1") (pintype "passive"))
    )
    (net (code "73") (name "Net-(LED4-PadA)") (class "Default")
      (node (ref "LED4") (pin "A") (pinfunction "A_A") (pintype "passive"))
      (node (ref "R41") (pin "1") (pinfunction "1_1") (pintype "passive"))
    )
    (net (code "74") (name "Net-(LED5-PadA)") (class "Default")
      (node (ref "LED5") (pin "A") (pinfunction "A_A") (pintype "passive"))
      (node (ref "R42") (pin "1") (pinfunction "1_1") (pintype "passive"))
    )
    (net (code "75") (name "Net-(LED6-PadA)") (class "Default")
      (node (ref "LED6") (pin "A") (pinfunction "A_A") (pintype "passive"))
      (node (ref "R43") (pin "1") (pinfunction "1_1") (pintype "passive"))
    )
    (net (code "76") (name "Net-(R41-Pad2)") (class "Default")
      (node (ref "R41") (pin "2") (pinfunction "2_2") (pintype "passive"))
      (node (ref "U$1") (pin "D10") (pinfunction "D10_D10") (pintype "bidirectional"))
    )
    (net (code "77") (name "Net-(R42-Pad2)") (class "Default")
      (node (ref "R42") (pin "2") (pinfunction "2_2") (pintype "passive"))
      (node (ref "U$1") (pin "D11") (pinfunction "D11_D11") (pintype "bidirectional"))
    )
    (net (code "78") (name "Net-(R43-Pad2)") (class "Default")
      (node (ref "R43") (pin "2") (pinfunction "2_2") (pintype "passive"))
      (node (ref "U$1") (pin "D12") (pinfunction "D12_D12") (pintype "bidirectional"))
    )
    (net (code "79") (name "unconnected-(DIS1-DB0-Pad7)") (class "Default")
      (node (ref "DIS1") (pin "7") (pinfunction "DB0_7") (pintype "bidirectional"))
    )
    (net (code "80") (name "unconnected-(DIS1-DB1-Pad8)") (class "Default")
      (node (ref "DIS1") (pin "8") (pinfunction "DB1_8") (pintype "bidirectional"))
    )
    (net (code "81") (name "unconnected-(DIS1-DB2-Pad9)") (class "Default")
      (node (ref "DIS1") (pin "9") (pinfunction "DB2_9") (pintype "bidirectional"))
    )
    (net (code "82") (name "unconnected-(DIS1-DB3-Pad10)") (class "Default")
      (node (ref "DIS1") (pin "10") (pinfunction "DB3_10") (pintype "bidirectional"))
    )
    (net (code "83") (name "unconnected-(JP2-Pad2)") (class "Default")
      (node (ref "JP2") (pin "2") (pinfunction "2_2") (pintype "passive"))
    )
    (net (code "84") (name "unconnected-(JP2-Pad3)") (class "Default")
      (node (ref "JP2") (pin "3") (pinfunction "3_3") (pintype "passive"))
    )
    (net (code "85") (name "unconnected-(JP2-Pad5)") (class "Default")
      (node (ref "JP2") (pin "5") (pinfunction "5_5") (pintype "passive"))
    )
    (net (code "86") (name "unconnected-(JP2-Pad7)") (class "Default")
      (node (ref "JP2") (pin "7") (pinfunction "7_7") (pintype "passive"))
    )
    (net (code "87") (name "unconnected-(JP2-Pad9)") (class "Default")
      (node (ref "JP2") (pin "9") (pinfunction "9_9") (pintype "passive"))
    )
    (net (code "88") (name "unconnected-(JP2-Pad11)") (class "Default")
      (node (ref "JP2") (pin "11") (pinfunction "11_11") (pintype "passive"))
    )
    (net (code "89") (name "unconnected-(JP2-Pad13)") (class "Default")
      (node (ref "JP2") (pin "13") (pinfunction "13_13") (pintype "passive"))
    )
    (net (code "90") (name "unconnected-(JP2-Pad17)") (class "Default")
      (node (ref "JP2") (pin "17") (pinfunction "17_17") (pintype "passive"))
    )
    (net (code "91") (name "unconnected-(JP2-Pad19)") (class "Default")
      (node (ref "JP2") (pin "19") (pinfunction "19_19") (pintype "passive"))
    )
    (net (code "92") (name "unconnected-(JP2-Pad21)") (class "Default")
      (node (ref "JP2") (pin "21") (pinfunction "21_21") (pintype "passive"))
    )
    (net (code "93") (name "unconnected-(JP2-Pad25)") (class "Default")
      (node (ref "JP2") (pin "25") (pinfunction "25_25") (pintype "passive"))
    )
    (net (code "94") (name "unconnected-(JP2-Pad27)") (class "Default")
      (node (ref "JP2") (pin "27") (pinfunction "27_27") (pintype "passive"))
    )
    (net (code "95") (name "unconnected-(JP2-Pad29)") (class "Default")
      (node (ref "JP2") (pin "29") (pinfunction "29_29") (pintype "passive"))
    )
    (net (code "96") (name "unconnected-(JP2-Pad33)") (class "Default")
      (node (ref "JP2") (pin "33") (pinfunction "33_33") (pintype "passive"))
    )
    (net (code "97") (name "unconnected-(JP4-Pad1)") (class "Default")
      (node (ref "JP4") (pin "1") (pinfunction "1_1") (pintype "passive"))
    )
    (net (code "98") (name "unconnected-(JP4-Pad6)") (class "Default")
      (node (ref "JP4") (pin "6") (pinfunction "6_6") (pintype "passive"))
    )
    (net (code "99") (name "unconnected-(U$1-+3V3.1-Pad3V3.1)") (class "Default")
      (node (ref "U$1") (pin "3V3.1") (pinfunction "+3V3.1_3V3.1") (pintype "bidirectional"))
    )
    (net (code "100") (name "unconnected-(U$1-+3V3.2-Pad3V3.2)") (class "Default")
      (node (ref "U$1") (pin "3V3.2") (pinfunction "+3V3.2_3V3.2") (pintype "bidirectional"))
    )
    (net (code "101") (name "unconnected-(U$1-AREF-PadAREF.1)") (class "Default")
      (node (ref "U$1") (pin "AREF.1") (pinfunction "AREF_AREF.1") (pintype "bidirectional"))
    )
    (net (code "102") (name "unconnected-(U$1-PadA0)") (class "Default")
      (node (ref "U$1") (pin "A0") (pinfunction "A0_A0") (pintype "bidirectional"))
    )
    (net (code "103") (name "unconnected-(U$1-PadA1)") (class "Default")
      (node (ref "U$1") (pin "A1") (pinfunction "A1_A1") (pintype "bidirectional"))
    )
    (net (code "104") (name "unconnected-(U$1-PadA2)") (class "Default")
      (node (ref "U$1") (pin "A2") (pinfunction "A2_A2") (pintype "bidirectional"))
    )
    (net (code "105") (name "unconnected-(U$1-PadA3)") (class "Default")
      (node (ref "U$1") (pin "A3") (pinfunction "A3_A3") (pintype "bidirectional"))
    )
    (net (code "106") (name "unconnected-(U$1-PadA4)") (class "Default")
      (node (ref "U$1") (pin "A4") (pinfunction "A4_A4") (pintype "bidirectional"))
    )
    (net (code "107") (name "unconnected-(U$1-PadA5)") (class "Default")
      (node (ref "U$1") (pin "A5") (pinfunction "A5_A5") (pintype "bidirectional"))
    )
    (net (code "108") (name "unconnected-(U$1-PadA6)") (class "Default")
      (node (ref "U$1") (pin "A6") (pinfunction "A6_A6") (pintype "bidirectional"))
    )
    (net (code "109") (name "unconnected-(U$1-PadA7)") (class "Default")
      (node (ref "U$1") (pin "A7") (pinfunction "A7_A7") (pintype "bidirectional"))
    )
    (net (code "110") (name "unconnected-(U$1-PadA8)") (class "Default")
      (node (ref "U$1") (pin "A8") (pinfunction "A8_A8") (pintype "bidirectional"))
    )
    (net (code "111") (name "unconnected-(U$1-PadA9)") (class "Default")
      (node (ref "U$1") (pin "A9") (pinfunction "A9_A9") (pintype "bidirectional"))
    )
    (net (code "112") (name "unconnected-(U$1-PadA10)") (class "Default")
      (node (ref "U$1") (pin "A10") (pinfunction "A10_A10") (pintype "bidirectional"))
    )
    (net (code "113") (name "unconnected-(U$1-PadA11)") (class "Default")
      (node (ref "U$1") (pin "A11") (pinfunction "A11_A11") (pintype "bidirectional"))
    )
    (net (code "114") (name "unconnected-(U$1-PadA12)") (class "Default")
      (node (ref "U$1") (pin "A12") (pinfunction "A12_A12") (pintype "bidirectional"))
    )
    (net (code "115") (name "unconnected-(U$1-PadA13)") (class "Default")
      (node (ref "U$1") (pin "A13") (pinfunction "A13_A13") (pintype "bidirectional"))
    )
    (net (code "116") (name "unconnected-(U$1-PadD13)") (class "Default")
      (node (ref "U$1") (pin "D13") (pinfunction "D13_D13") (pintype "bidirectional"))
    )
    (net (code "117") (name "unconnected-(U$1-PadD18)") (class "Default")
      (node (ref "U$1") (pin "D18") (pinfunction "D18_D18") (pintype "bidirectional"))
    )
    (net (code "118") (name "unconnected-(U$1-PadD19)") (class "Default")
      (node (ref "U$1") (pin "D19") (pinfunction "D19_D19") (pintype "bidirectional"))
    )
    (net (code "119") (name "unconnected-(U$1-PadRST)") (class "Default")
      (node (ref "U$1") (pin "RST") (pinfunction "RST_RST") (pintype "bidirectional"))
    )
    (net (code "120") (name "unconnected-(U$1-PadRX)") (class "Default")
      (node (ref "U$1") (pin "RX") (pinfunction "RX_RX") (pintype "bidirectional"))
    )
    (net (code "121") (name "unconnected-(U$1-PadTX)") (class "Default")
      (node (ref "U$1") (pin "TX") (pinfunction "TX_TX") (pintype "bidirectional"))
    )
    (net (code "122") (name "unconnected-(U$1-PadVIN.1)") (class "Default")
      (node (ref "U$1") (pin "VIN.1") (pinfunction "VIN.1_VIN.1") (pintype "bidirectional"))
    )
    (net (code "123") (name "unconnected-(U$1-PadVIN.2)") (class "Default")
      (node (ref "U$1") (pin "VIN.2") (pinfunction "VIN.2_VIN.2") (pintype "bidirectional"))
    )
    (net (code "124") (name "unconnected-(U$2-P$1-Pad3V0)") (class "Default")
      (node (ref "U$2") (pin "3V0") (pinfunction "P$1_3V0") (pintype "bidirectional"))
    )
    (net (code "125") (name "unconnected-(U$2-P$2-PadADR)") (class "Default")
      (node (ref "U$2") (pin "ADR") (pinfunction "P$2_ADR") (pintype "bidirectional"))
    )
    (net (code "126") (name "unconnected-(U$2-P$4-PadINT)") (class "Default")
      (node (ref "U$2") (pin "INT") (pinfunction "P$4_INT") (pintype "bidirectional"))
    )
    (net (code "127") (name "unconnected-(U$2-P$5-PadPS0)") (class "Default")
      (node (ref "U$2") (pin "PS0") (pinfunction "P$5_PS0") (pintype "bidirectional"))
    )
    (net (code "128") (name "unconnected-(U$2-P$6-PadPS1)") (class "Default")
      (node (ref "U$2") (pin "PS1") (pinfunction "P$6_PS1") (pintype "bidirectional"))
    )
    (net (code "129") (name "unconnected-(U$2-P$7-PadRST)") (class "Default")
      (node (ref "U$2") (pin "RST") (pinfunction "P$7_RST") (pintype "bidirectional"))
    )
  )
)
